# test1.net
KiCad netlist of a schematic drawn in EAGLE
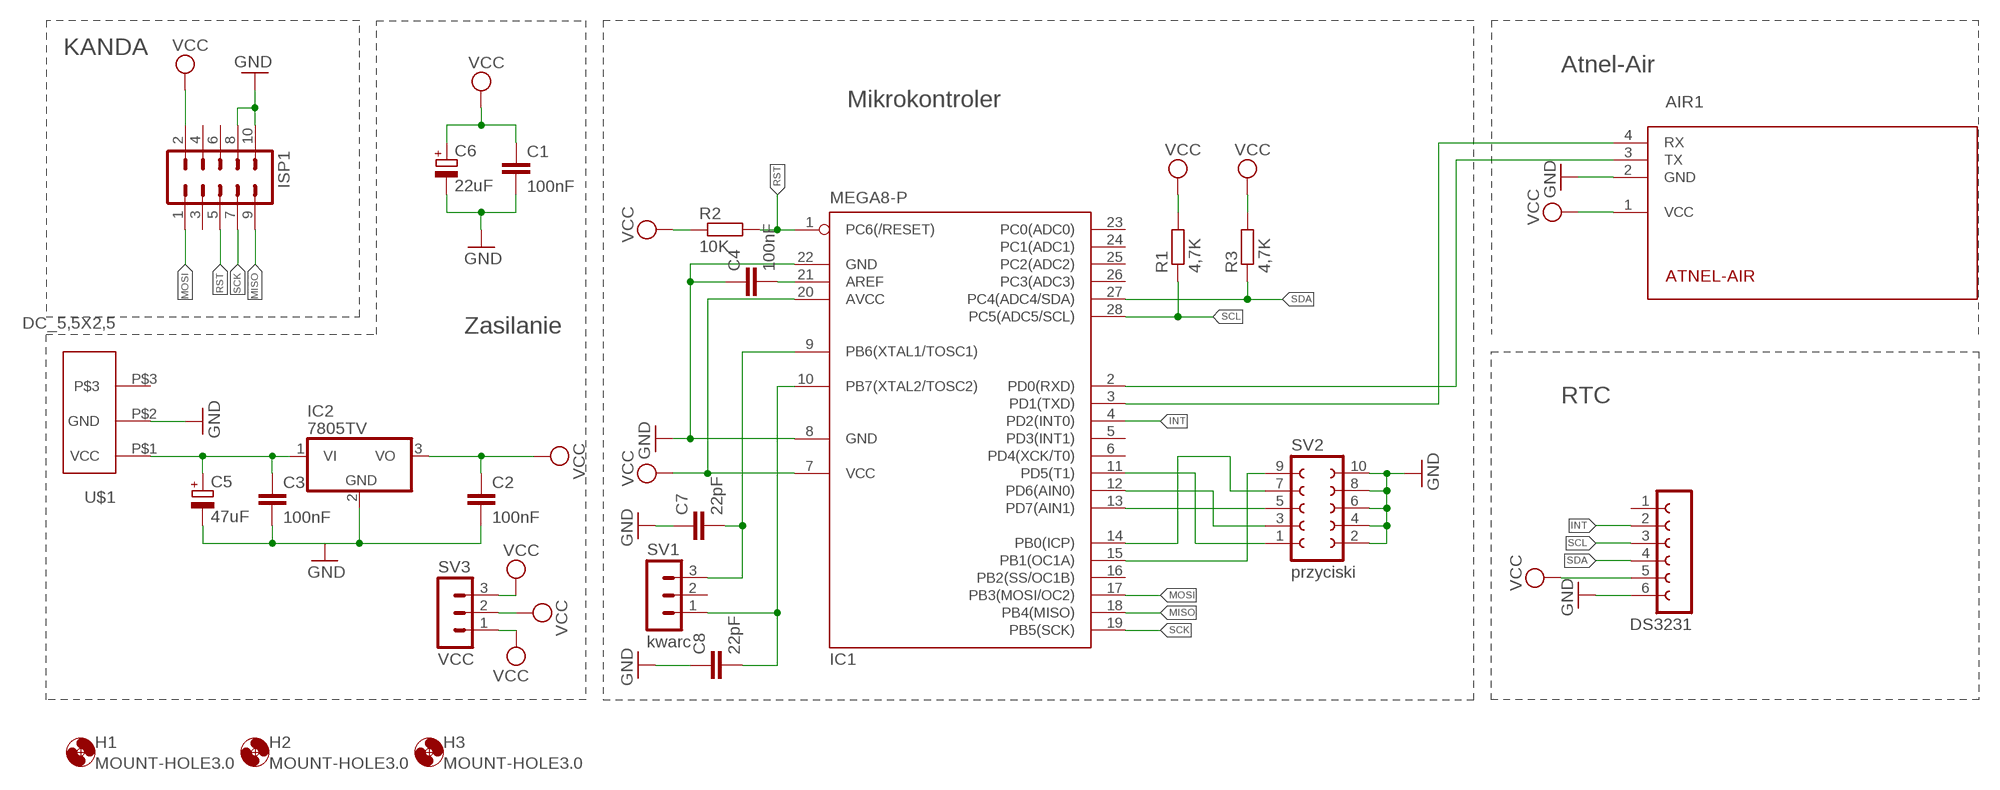
[diagram p0: schematic, sheet 1]

(export (version "E")
  (design (tool "Eeschema 10.0.6"))
  (components
    (comp (ref "AIR1")
      (value "ATNEL-AIR")
      (footprint "eagle-import:ATNEL-AIR")
      (libsource (lib "eagle-import") (part "ATNEL-AIR"))
    )
    (comp (ref "C1")
      (value "100nF")
      (footprint "eagle-import:C025-024X044")
      (libsource (lib "eagle-import") (part "C-EU025-024X044"))
    )
    (comp (ref "C2")
      (value "100nF")
      (footprint "eagle-import:C025-024X044")
      (libsource (lib "eagle-import") (part "C-EU025-024X044"))
    )
    (comp (ref "C3")
      (value "100nF")
      (footprint "eagle-import:C025-024X044")
      (libsource (lib "eagle-import") (part "C-EU025-024X044"))
    )
    (comp (ref "C4")
      (value "100nF")
      (footprint "eagle-import:C025-024X044")
      (libsource (lib "eagle-import") (part "C-EU025-024X044"))
    )
    (comp (ref "C5")
      (value "47uF")
      (footprint "eagle-import:B45181A")
      (libsource (lib "eagle-import") (part "CPOL-EUB45181A"))
    )
    (comp (ref "C6")
      (value "22uF")
      (footprint "eagle-import:B45181A")
      (libsource (lib "eagle-import") (part "CPOL-EUB45181A"))
    )
    (comp (ref "C7")
      (value "22pF")
      (footprint "eagle-import:C025-024X044")
      (libsource (lib "eagle-import") (part "C-EU025-024X044"))
    )
    (comp (ref "C8")
      (value "22pF")
      (footprint "eagle-import:C025-024X044")
      (libsource (lib "eagle-import") (part "C-EU025-024X044"))
    )
    (comp (ref "DS3231")
      (value "FE06-1")
      (footprint "eagle-import:FE06")
      (libsource (lib "eagle-import") (part "FE06-1"))
    )
    (comp (ref "H1")
      (value "MOUNT-HOLE3.0")
      (footprint "eagle-import:3,0")
      (libsource (lib "eagle-import") (part "MOUNT-HOLE3.0"))
    )
    (comp (ref "H2")
      (value "MOUNT-HOLE3.0")
      (footprint "eagle-import:3,0")
      (libsource (lib "eagle-import") (part "MOUNT-HOLE3.0"))
    )
    (comp (ref "H3")
      (value "MOUNT-HOLE3.0")
      (footprint "eagle-import:3,0")
      (libsource (lib "eagle-import") (part "MOUNT-HOLE3.0"))
    )
    (comp (ref "IC1")
      (value "MEGA8-P")
      (footprint "eagle-import:DIL28-3")
      (libsource (lib "eagle-import") (part "MEGA8-P"))
    )
    (comp (ref "IC2")
      (value "7805TV")
      (footprint "eagle-import:TO220V")
      (libsource (lib "eagle-import") (part "78TV05"))
    )
    (comp (ref "ISP1")
      (value "ML10")
      (footprint "eagle-import:ML10")
      (libsource (lib "eagle-import") (part "ML10"))
    )
    (comp (ref "R1")
      (value "4,7K")
      (footprint "eagle-import:0204_7")
      (libsource (lib "eagle-import") (part "R-EU_0204/7"))
    )
    (comp (ref "R2")
      (value "10K")
      (footprint "eagle-import:0204_7")
      (libsource (lib "eagle-import") (part "R-EU_0204/7"))
    )
    (comp (ref "R3")
      (value "4,7K")
      (footprint "eagle-import:0204_7")
      (libsource (lib "eagle-import") (part "R-EU_0204/7"))
    )
    (comp (ref "SV1")
      (value "kwarc")
      (footprint "eagle-import:MA03-1")
      (libsource (lib "eagle-import") (part "MA03-1"))
    )
    (comp (ref "SV2")
      (value "przyciski")
      (footprint "eagle-import:FE05-2")
      (libsource (lib "eagle-import") (part "FE05-2"))
    )
    (comp (ref "SV3")
      (value "VCC")
      (footprint "eagle-import:MA03-1")
      (libsource (lib "eagle-import") (part "MA03-1"))
    )
    (comp (ref "U$1")
      (value "DC_5,5X2,5")
      (footprint "eagle-import:DC_5,5X2,5")
      (libsource (lib "eagle-import") (part "DC_5,5X2,5"))
    )
  )
  (nets
    (net (code "1") (name "GND") (class "Default")
      (node (ref "AIR1") (pin "2") (pinfunction "GND_2") (pintype "bidirectional"))
      (node (ref "C1") (pin "2") (pinfunction "2_2") (pintype "passive"))
      (node (ref "C2") (pin "2") (pinfunction "2_2") (pintype "passive"))
      (node (ref "C3") (pin "2") (pinfunction "2_2") (pintype "passive"))
      (node (ref "C4") (pin "1") (pinfunction "1_1") (pintype "passive"))
      (node (ref "C5") (pin "-") (pinfunction "-_-") (pintype "passive"))
      (node (ref "C6") (pin "-") (pinfunction "-_-") (pintype "passive"))
      (node (ref "C7") (pin "1") (pinfunction "1_1") (pintype "passive"))
      (node (ref "C8") (pin "1") (pinfunction "1_1") (pintype "passive"))
      (node (ref "DS3231") (pin "6") (pinfunction "6_6") (pintype "passive"))
      (node (ref "IC1") (pin "22") (pinfunction "GND_22") (pintype "power_in"))
      (node (ref "IC1") (pin "8") (pinfunction "GND_8") (pintype "power_in"))
      (node (ref "IC2") (pin "2") (pinfunction "GND_2") (pintype "passive"))
      (node (ref "ISP1") (pin "10") (pinfunction "10_10") (pintype "passive"))
      (node (ref "ISP1") (pin "8") (pinfunction "8_8") (pintype "passive"))
      (node (ref "SV2") (pin "10") (pinfunction "10_10") (pintype "passive"))
      (node (ref "SV2") (pin "2") (pinfunction "2_2") (pintype "passive"))
      (node (ref "SV2") (pin "4") (pinfunction "4_4") (pintype "passive"))
      (node (ref "SV2") (pin "6") (pinfunction "6_6") (pintype "passive"))
      (node (ref "SV2") (pin "8") (pinfunction "8_8") (pintype "passive"))
      (node (ref "U$1") (pin "P$2") (pinfunction "GND_P$2") (pintype "bidirectional"))
    )
    (net (code "2") (name "INT") (class "Default")
      (node (ref "DS3231") (pin "2") (pinfunction "2_2") (pintype "passive"))
      (node (ref "IC1") (pin "4") (pinfunction "PD2(INT0)_4") (pintype "bidirectional"))
    )
    (net (code "3") (name "MISO") (class "Default")
      (node (ref "IC1") (pin "18") (pinfunction "PB4(MISO)_18") (pintype "bidirectional"))
      (node (ref "ISP1") (pin "9") (pinfunction "9_9") (pintype "passive"))
    )
    (net (code "4") (name "MOSI") (class "Default")
      (node (ref "IC1") (pin "17") (pinfunction "PB3(MOSI/OC2)_17") (pintype "bidirectional"))
      (node (ref "ISP1") (pin "1") (pinfunction "1_1") (pintype "passive"))
    )
    (net (code "5") (name "Net-(AIR1-RX)") (class "Default")
      (node (ref "AIR1") (pin "4") (pinfunction "RX_4") (pintype "output"))
      (node (ref "IC1") (pin "3") (pinfunction "PD1(TXD)_3") (pintype "bidirectional"))
    )
    (net (code "6") (name "Net-(AIR1-TX)") (class "Default")
      (node (ref "AIR1") (pin "3") (pinfunction "TX_3") (pintype "input"))
      (node (ref "IC1") (pin "2") (pinfunction "PD0(RXD)_2") (pintype "bidirectional"))
    )
    (net (code "7") (name "Net-(IC1-AREF)") (class "Default")
      (node (ref "C4") (pin "2") (pinfunction "2_2") (pintype "passive"))
      (node (ref "IC1") (pin "21") (pinfunction "AREF_21") (pintype "passive"))
    )
    (net (code "8") (name "Net-(IC1-PB0(ICP))") (class "Default")
      (node (ref "IC1") (pin "14") (pinfunction "PB0(ICP)_14") (pintype "bidirectional"))
      (node (ref "SV2") (pin "7") (pinfunction "7_7") (pintype "passive"))
    )
    (net (code "9") (name "Net-(IC1-PB1(OC1A))") (class "Default")
      (node (ref "IC1") (pin "15") (pinfunction "PB1(OC1A)_15") (pintype "bidirectional"))
      (node (ref "SV2") (pin "9") (pinfunction "9_9") (pintype "passive"))
    )
    (net (code "10") (name "Net-(IC1-PB6(XTAL1{slash}TOSC1))") (class "Default")
      (node (ref "C7") (pin "2") (pinfunction "2_2") (pintype "passive"))
      (node (ref "IC1") (pin "9") (pinfunction "PB6(XTAL1/TOSC1)_9") (pintype "bidirectional"))
      (node (ref "SV1") (pin "3") (pinfunction "3_3") (pintype "passive"))
    )
    (net (code "11") (name "Net-(IC1-PB7(XTAL2{slash}TOSC2))") (class "Default")
      (node (ref "C8") (pin "2") (pinfunction "2_2") (pintype "passive"))
      (node (ref "IC1") (pin "10") (pinfunction "PB7(XTAL2/TOSC2)_10") (pintype "bidirectional"))
      (node (ref "SV1") (pin "1") (pinfunction "1_1") (pintype "passive"))
    )
    (net (code "12") (name "Net-(IC1-PD5(T1))") (class "Default")
      (node (ref "IC1") (pin "11") (pinfunction "PD5(T1)_11") (pintype "bidirectional"))
      (node (ref "SV2") (pin "1") (pinfunction "1_1") (pintype "passive"))
    )
    (net (code "13") (name "Net-(IC1-PD6(AIN0))") (class "Default")
      (node (ref "IC1") (pin "12") (pinfunction "PD6(AIN0)_12") (pintype "bidirectional"))
      (node (ref "SV2") (pin "3") (pinfunction "3_3") (pintype "passive"))
    )
    (net (code "14") (name "Net-(IC1-PD7(AIN1))") (class "Default")
      (node (ref "IC1") (pin "13") (pinfunction "PD7(AIN1)_13") (pintype "bidirectional"))
      (node (ref "SV2") (pin "5") (pinfunction "5_5") (pintype "passive"))
    )
    (net (code "15") (name "Net-(IC2-VI)") (class "Default")
      (node (ref "C3") (pin "1") (pinfunction "1_1") (pintype "passive"))
      (node (ref "C5") (pin "+") (pinfunction "+_+") (pintype "passive"))
      (node (ref "IC2") (pin "1") (pinfunction "VI_1") (pintype "input"))
      (node (ref "U$1") (pin "P$1") (pinfunction "VCC_P$1") (pintype "bidirectional"))
    )
    (net (code "16") (name "RST") (class "Default")
      (node (ref "IC1") (pin "1") (pinfunction "PC6(/RESET)_1") (pintype "bidirectional"))
      (node (ref "ISP1") (pin "5") (pinfunction "5_5") (pintype "passive"))
      (node (ref "R2") (pin "2") (pinfunction "2_2") (pintype "passive"))
    )
    (net (code "17") (name "SCK") (class "Default")
      (node (ref "IC1") (pin "19") (pinfunction "PB5(SCK)_19") (pintype "bidirectional"))
      (node (ref "ISP1") (pin "7") (pinfunction "7_7") (pintype "passive"))
    )
    (net (code "18") (name "SCL") (class "Default")
      (node (ref "DS3231") (pin "3") (pinfunction "3_3") (pintype "passive"))
      (node (ref "IC1") (pin "28") (pinfunction "PC5(ADC5/SCL)_28") (pintype "bidirectional"))
      (node (ref "R1") (pin "1") (pinfunction "1_1") (pintype "passive"))
    )
    (net (code "19") (name "SDA") (class "Default")
      (node (ref "DS3231") (pin "4") (pinfunction "4_4") (pintype "passive"))
      (node (ref "IC1") (pin "27") (pinfunction "PC4(ADC4/SDA)_27") (pintype "bidirectional"))
      (node (ref "R3") (pin "1") (pinfunction "1_1") (pintype "passive"))
    )
    (net (code "20") (name "VCC") (class "Default")
      (node (ref "AIR1") (pin "1") (pinfunction "VCC_1") (pintype "bidirectional"))
      (node (ref "C1") (pin "1") (pinfunction "1_1") (pintype "passive"))
      (node (ref "C2") (pin "1") (pinfunction "1_1") (pintype "passive"))
      (node (ref "C6") (pin "+") (pinfunction "+_+") (pintype "passive"))
      (node (ref "DS3231") (pin "5") (pinfunction "5_5") (pintype "passive"))
      (node (ref "IC1") (pin "20") (pinfunction "AVCC_20") (pintype "power_in"))
      (node (ref "IC1") (pin "7") (pinfunction "VCC_7") (pintype "power_in"))
      (node (ref "IC2") (pin "3") (pinfunction "VO_3") (pintype "passive"))
      (node (ref "ISP1") (pin "2") (pinfunction "2_2") (pintype "passive"))
      (node (ref "R1") (pin "2") (pinfunction "2_2") (pintype "passive"))
      (node (ref "R2") (pin "1") (pinfunction "1_1") (pintype "passive"))
      (node (ref "R3") (pin "2") (pinfunction "2_2") (pintype "passive"))
      (node (ref "SV3") (pin "1") (pinfunction "1_1") (pintype "passive"))
      (node (ref "SV3") (pin "2") (pinfunction "2_2") (pintype "passive"))
      (node (ref "SV3") (pin "3") (pinfunction "3_3") (pintype "passive"))
    )
    (net (code "21") (name "unconnected-(DS3231-Pad1)") (class "Default")
      (node (ref "DS3231") (pin "1") (pinfunction "1_1") (pintype "passive"))
    )
    (net (code "22") (name "unconnected-(IC1-PB2(SS{slash}OC1B)-Pad16)") (class "Default")
      (node (ref "IC1") (pin "16") (pinfunction "PB2(SS/OC1B)_16") (pintype "bidirectional"))
    )
    (net (code "23") (name "unconnected-(IC1-PC0(ADC0)-Pad23)") (class "Default")
      (node (ref "IC1") (pin "23") (pinfunction "PC0(ADC0)_23") (pintype "bidirectional"))
    )
    (net (code "24") (name "unconnected-(IC1-PC1(ADC1)-Pad24)") (class "Default")
      (node (ref "IC1") (pin "24") (pinfunction "PC1(ADC1)_24") (pintype "bidirectional"))
    )
    (net (code "25") (name "unconnected-(IC1-PC2(ADC2)-Pad25)") (class "Default")
      (node (ref "IC1") (pin "25") (pinfunction "PC2(ADC2)_25") (pintype "bidirectional"))
    )
    (net (code "26") (name "unconnected-(IC1-PC3(ADC3)-Pad26)") (class "Default")
      (node (ref "IC1") (pin "26") (pinfunction "PC3(ADC3)_26") (pintype "bidirectional"))
    )
    (net (code "27") (name "unconnected-(IC1-PD3(INT1)-Pad5)") (class "Default")
      (node (ref "IC1") (pin "5") (pinfunction "PD3(INT1)_5") (pintype "bidirectional"))
    )
    (net (code "28") (name "unconnected-(IC1-PD4(XCK{slash}T0)-Pad6)") (class "Default")
      (node (ref "IC1") (pin "6") (pinfunction "PD4(XCK/T0)_6") (pintype "bidirectional"))
    )
    (net (code "29") (name "unconnected-(ISP1-Pad3)") (class "Default")
      (node (ref "ISP1") (pin "3") (pinfunction "3_3") (pintype "passive"))
    )
    (net (code "30") (name "unconnected-(ISP1-Pad4)") (class "Default")
      (node (ref "ISP1") (pin "4") (pinfunction "4_4") (pintype "passive"))
    )
    (net (code "31") (name "unconnected-(ISP1-Pad6)") (class "Default")
      (node (ref "ISP1") (pin "6") (pinfunction "6_6") (pintype "passive"))
    )
    (net (code "32") (name "unconnected-(SV1-Pad2)") (class "Default")
      (node (ref "SV1") (pin "2") (pinfunction "2_2") (pintype "passive"))
    )
    (net (code "33") (name "unconnected-(U$1-PadP$3)") (class "Default")
      (node (ref "U$1") (pin "P$3") (pinfunction "P$3_P$3") (pintype "bidirectional"))
    )
  )
)
